# Project_Canary_V3_5.net
KiCad netlist of a schematic drawn in EAGLE
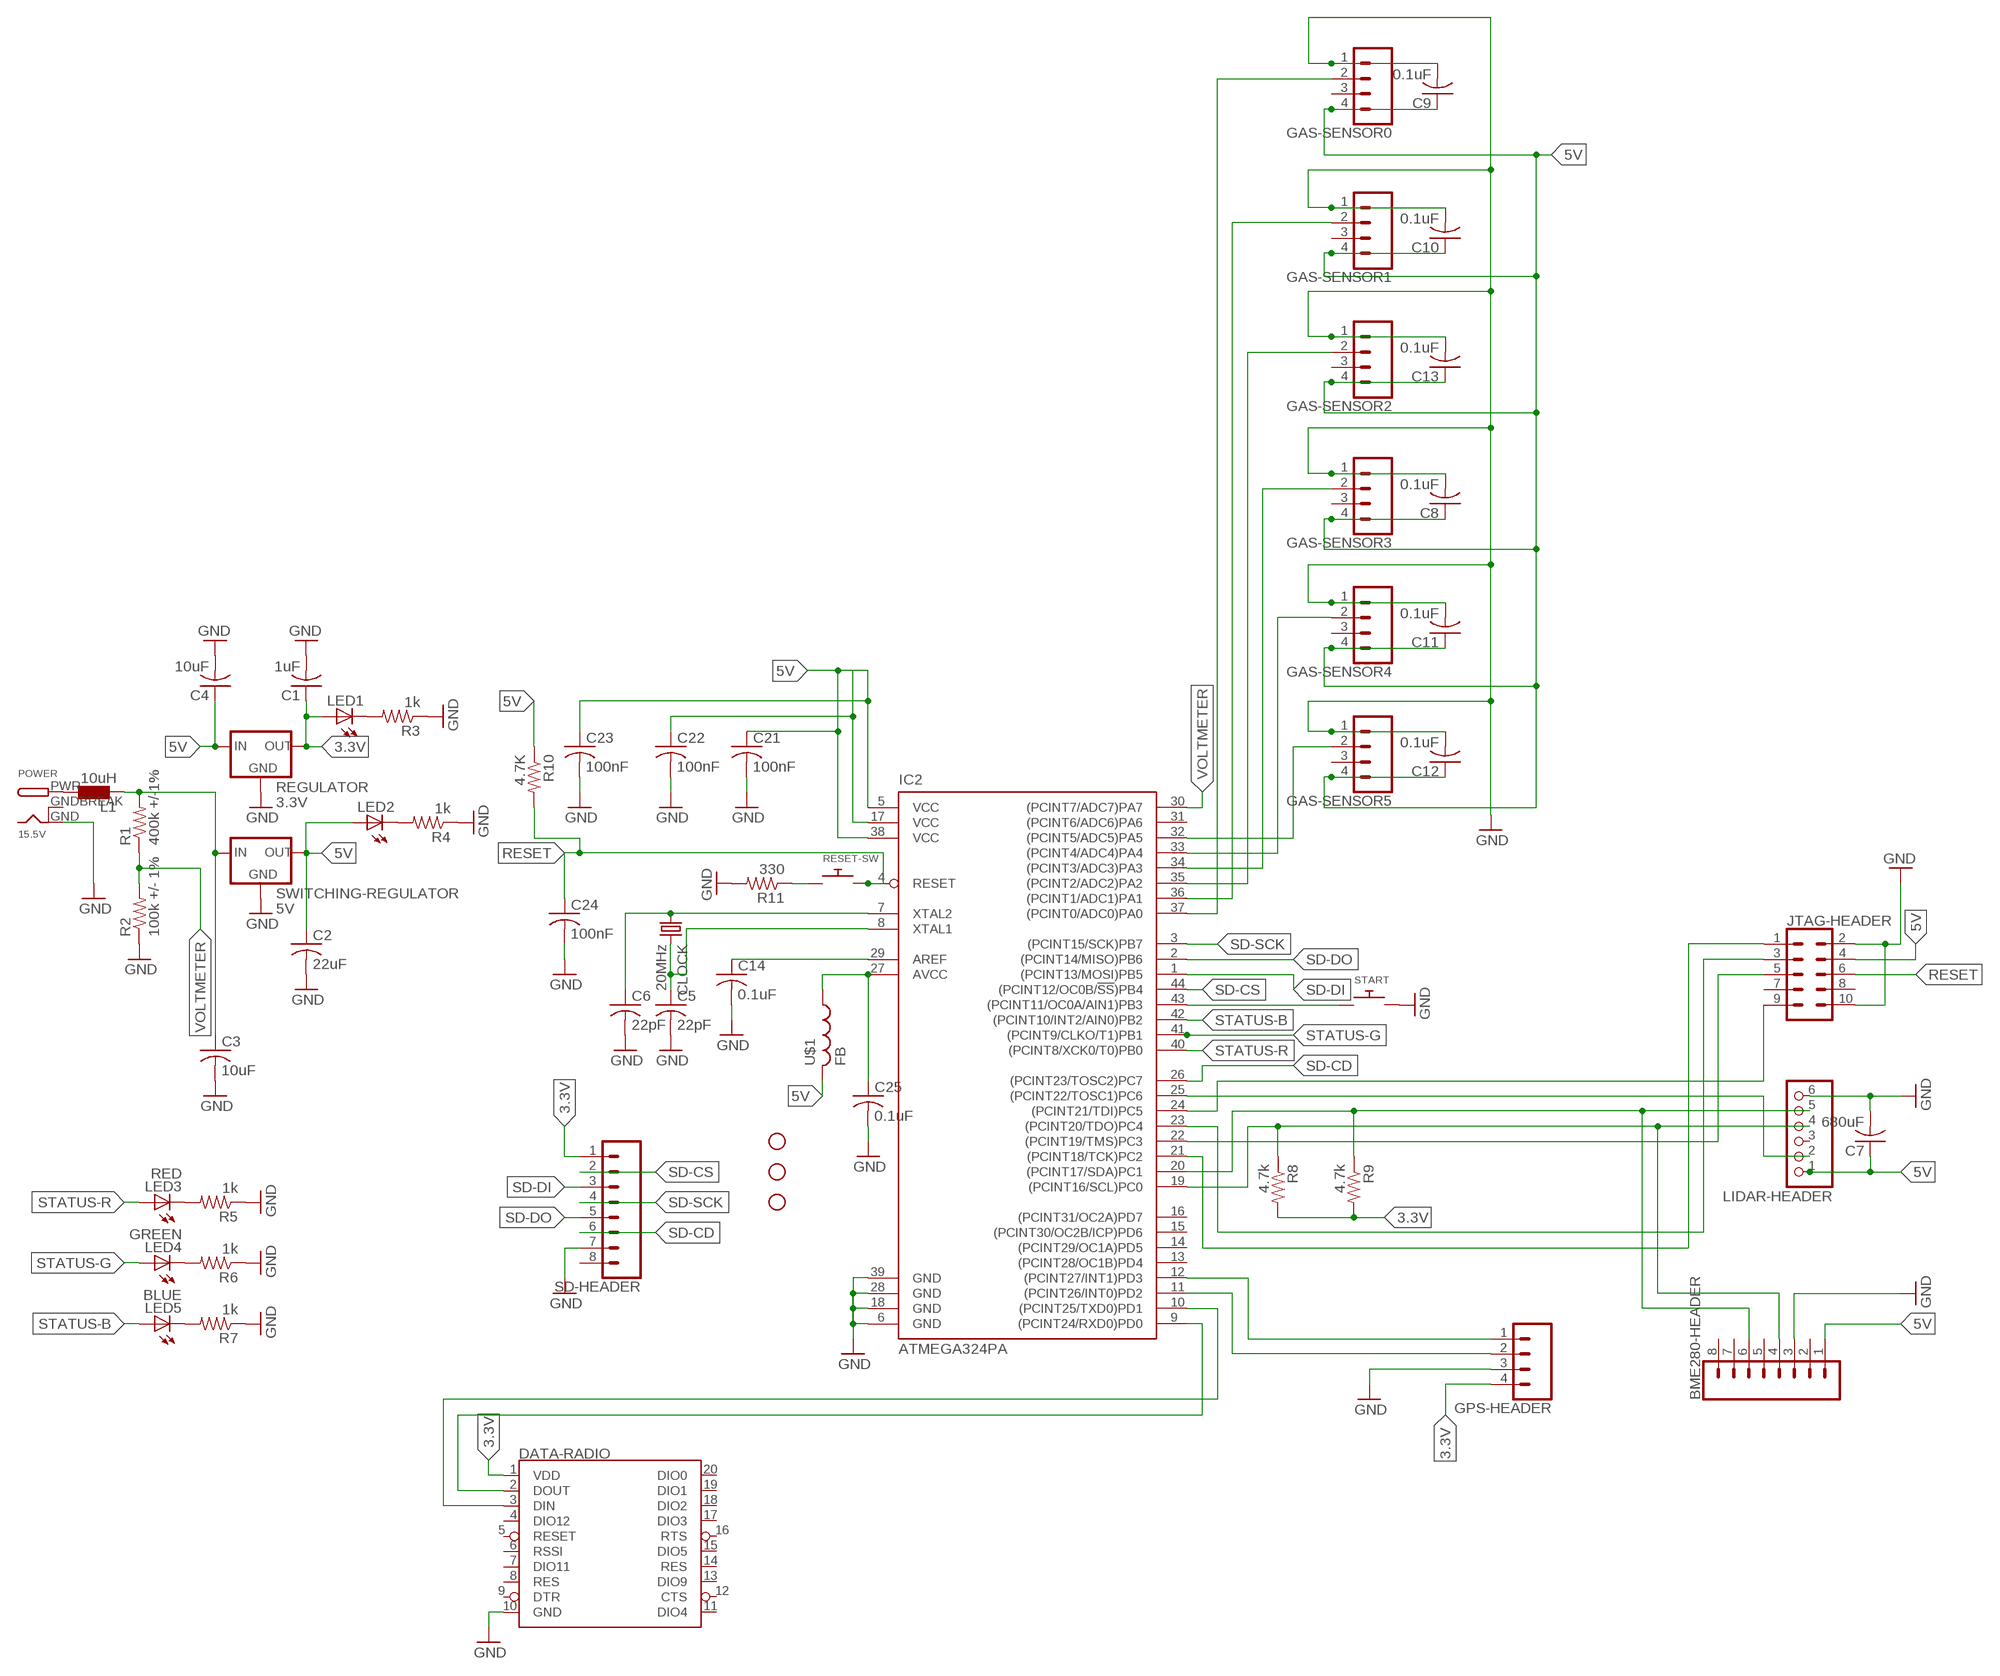
[diagram p0: schematic, sheet 1]

(export (version "E")
  (design (tool "Eeschema 10.0.6"))
  (components
    (comp (ref "BME280-HEADER")
      (value "CONN_08\"")
      (footprint "eagle-import:1X08")
      (libsource (lib "eagle-import") (part "CONN_08{dblquote}"))
    )
    (comp (ref "C1")
      (value "1uF")
      (footprint "eagle-import:C0805")
      (libsource (lib "eagle-import") (part "C-USC0805"))
    )
    (comp (ref "C2")
      (value "22uF")
      (footprint "eagle-import:C0603")
      (libsource (lib "eagle-import") (part "C-USC0603"))
    )
    (comp (ref "C3")
      (value "10uF")
      (footprint "eagle-import:C0805")
      (libsource (lib "eagle-import") (part "C-USC0805"))
    )
    (comp (ref "C4")
      (value "10uF")
      (footprint "eagle-import:C0603")
      (libsource (lib "eagle-import") (part "C-USC0603"))
    )
    (comp (ref "C5")
      (value "22pF")
      (footprint "eagle-import:C0603")
      (libsource (lib "eagle-import") (part "C-USC0603"))
    )
    (comp (ref "C6")
      (value "22pF")
      (footprint "eagle-import:C0603")
      (libsource (lib "eagle-import") (part "C-USC0603"))
    )
    (comp (ref "C7")
      (value "680uF")
      (footprint "eagle-import:C0603")
      (libsource (lib "eagle-import") (part "C-USC0603"))
    )
    (comp (ref "C8")
      (value "0.1uF")
      (footprint "eagle-import:C0603")
      (libsource (lib "eagle-import") (part "C-USC0603"))
    )
    (comp (ref "C9")
      (value "0.1uF")
      (footprint "eagle-import:C0603")
      (libsource (lib "eagle-import") (part "C-USC0603"))
    )
    (comp (ref "C10")
      (value "0.1uF")
      (footprint "eagle-import:C0603")
      (libsource (lib "eagle-import") (part "C-USC0603"))
    )
    (comp (ref "C11")
      (value "0.1uF")
      (footprint "eagle-import:C0603")
      (libsource (lib "eagle-import") (part "C-USC0603"))
    )
    (comp (ref "C12")
      (value "0.1uF")
      (footprint "eagle-import:C0603")
      (libsource (lib "eagle-import") (part "C-USC0603"))
    )
    (comp (ref "C13")
      (value "0.1uF")
      (footprint "eagle-import:C0603")
      (libsource (lib "eagle-import") (part "C-USC0603"))
    )
    (comp (ref "C14")
      (value "0.1uF")
      (footprint "eagle-import:C0603")
      (libsource (lib "eagle-import") (part "C-USC0603"))
    )
    (comp (ref "C21")
      (value "100nF")
      (footprint "eagle-import:C0603")
      (libsource (lib "eagle-import") (part "C-USC0603"))
    )
    (comp (ref "C22")
      (value "100nF")
      (footprint "eagle-import:C0603")
      (libsource (lib "eagle-import") (part "C-USC0603"))
    )
    (comp (ref "C23")
      (value "100nF")
      (footprint "eagle-import:C0603")
      (libsource (lib "eagle-import") (part "C-USC0603"))
    )
    (comp (ref "C24")
      (value "100nF")
      (footprint "eagle-import:C0805")
      (libsource (lib "eagle-import") (part "C-USC0805"))
    )
    (comp (ref "C25")
      (value "0.1uF")
      (footprint "eagle-import:C0603")
      (libsource (lib "eagle-import") (part "C-USC0603"))
    )
    (comp (ref "CLOCK")
      (value "20MHz")
      (footprint "eagle-import:86SMX")
      (libsource (lib "eagle-import") (part "CRYSTAL68SMX"))
    )
    (comp (ref "DATA-RADIO")
      (value "XBEE")
      (footprint "eagle-import:XBEE")
      (libsource (lib "eagle-import") (part "XBEE"))
    )
    (comp (ref "GAS-SENSOR0")
      (value "CONN_04")
      (footprint "eagle-import:1X04")
      (libsource (lib "eagle-import") (part "CONN_04"))
    )
    (comp (ref "GAS-SENSOR1")
      (value "CONN_04")
      (footprint "eagle-import:1X04")
      (libsource (lib "eagle-import") (part "CONN_04"))
    )
    (comp (ref "GAS-SENSOR2")
      (value "CONN_04")
      (footprint "eagle-import:1X04")
      (libsource (lib "eagle-import") (part "CONN_04"))
    )
    (comp (ref "GAS-SENSOR3")
      (value "CONN_04")
      (footprint "eagle-import:1X04")
      (libsource (lib "eagle-import") (part "CONN_04"))
    )
    (comp (ref "GAS-SENSOR4")
      (value "CONN_04")
      (footprint "eagle-import:1X04")
      (libsource (lib "eagle-import") (part "CONN_04"))
    )
    (comp (ref "GAS-SENSOR5")
      (value "CONN_04")
      (footprint "eagle-import:1X04")
      (libsource (lib "eagle-import") (part "CONN_04"))
    )
    (comp (ref "GPS-HEADER")
      (value "CONN_04")
      (footprint "eagle-import:1X04")
      (libsource (lib "eagle-import") (part "CONN_04"))
    )
    (comp (ref "IC2")
      (value "ATMEGA324PA")
      (footprint "eagle-import:TQFP44")
      (fields (field (name "MPN") "ATMEGA644PV-10AU"))
      (libsource (lib "eagle-import") (part "ATMEGA644A"))
    )
    (comp (ref "JTAG-HEADER")
      (value "CONN_05X2PTH")
      (footprint "eagle-import:2X5")
      (libsource (lib "eagle-import") (part "CONN_05X2PTH"))
    )
    (comp (ref "L1")
      (value "10uH")
      (footprint "eagle-import:L1812")
      (libsource (lib "eagle-import") (part "L"))
    )
    (comp (ref "LED1")
      (value "LEDCHIP-LED0805")
      (footprint "eagle-import:CHIP-LED0805")
      (libsource (lib "eagle-import") (part "LEDCHIP-LED0805"))
    )
    (comp (ref "LED2")
      (value "LEDCHIP-LED0805")
      (footprint "eagle-import:CHIP-LED0805")
      (libsource (lib "eagle-import") (part "LEDCHIP-LED0805"))
    )
    (comp (ref "LED3")
      (value "RED")
      (footprint "eagle-import:CHIP-LED0805")
      (libsource (lib "eagle-import") (part "LEDCHIP-LED0805"))
    )
    (comp (ref "LED4")
      (value "GREEN")
      (footprint "eagle-import:CHIP-LED0805")
      (libsource (lib "eagle-import") (part "LEDCHIP-LED0805"))
    )
    (comp (ref "LED5")
      (value "BLUE")
      (footprint "eagle-import:CHIP-LED0805")
      (libsource (lib "eagle-import") (part "LEDCHIP-LED0805"))
    )
    (comp (ref "LIDAR-HEADER")
      (value "PINHD-1X6")
      (footprint "eagle-import:1X06")
      (libsource (lib "eagle-import") (part "PINHD-1X6"))
    )
    (comp (ref "MOUNT-HOLE1")
      (value "STAND-OFF")
      (footprint "eagle-import:STAND-OFF")
      (libsource (lib "eagle-import") (part "STAND-OFF"))
    )
    (comp (ref "MOUNT-HOLE2")
      (value "STAND-OFF")
      (footprint "eagle-import:STAND-OFF")
      (libsource (lib "eagle-import") (part "STAND-OFF"))
    )
    (comp (ref "MOUNT-HOLE3")
      (value "STAND-OFF")
      (footprint "eagle-import:STAND-OFF")
      (libsource (lib "eagle-import") (part "STAND-OFF"))
    )
    (comp (ref "POWER")
      (value "15.5V")
      (footprint "eagle-import:DCJACK_2MM_PTH")
      (libsource (lib "eagle-import") (part "DCBARRELPTH"))
    )
    (comp (ref "R1")
      (value "400k +/-1%")
      (footprint "eagle-import:M0805")
      (libsource (lib "eagle-import") (part "R-US_M0805"))
    )
    (comp (ref "R2")
      (value "100k +/- 1%")
      (footprint "eagle-import:M0805")
      (libsource (lib "eagle-import") (part "R-US_M0805"))
    )
    (comp (ref "R3")
      (value "1k")
      (footprint "eagle-import:M0805")
      (libsource (lib "eagle-import") (part "R-US_M0805"))
    )
    (comp (ref "R4")
      (value "1k")
      (footprint "eagle-import:M0805")
      (libsource (lib "eagle-import") (part "R-US_M0805"))
    )
    (comp (ref "R5")
      (value "1k")
      (footprint "eagle-import:M0805")
      (libsource (lib "eagle-import") (part "R-US_M0805"))
    )
    (comp (ref "R6")
      (value "1k")
      (footprint "eagle-import:M0805")
      (libsource (lib "eagle-import") (part "R-US_M0805"))
    )
    (comp (ref "R7")
      (value "1k")
      (footprint "eagle-import:M0805")
      (libsource (lib "eagle-import") (part "R-US_M0805"))
    )
    (comp (ref "R8")
      (value "4.7k")
      (footprint "eagle-import:M0805")
      (libsource (lib "eagle-import") (part "R-US_M0805"))
    )
    (comp (ref "R9")
      (value "4.7k")
      (footprint "eagle-import:M0805")
      (libsource (lib "eagle-import") (part "R-US_M0805"))
    )
    (comp (ref "R10")
      (value "4.7K")
      (footprint "eagle-import:M0805")
      (libsource (lib "eagle-import") (part "R-US_M0805"))
    )
    (comp (ref "R11")
      (value "330")
      (footprint "eagle-import:M0805")
      (libsource (lib "eagle-import") (part "R-US_M0805"))
    )
    (comp (ref "REGULATOR")
      (value "3.3V")
      (footprint "eagle-import:TO220-IGO")
      (libsource (lib "eagle-import") (part "V_REG_78XXSINK"))
    )
    (comp (ref "RESET-SW")
      (value "SWITCH_PUSHBUTTONSOFTTOUCHSMD_SJ")
      (footprint "eagle-import:PUSHBUTTON_SMD_SJ")
      (libsource (lib "eagle-import") (part "SWITCH_PUSHBUTTONSOFTTOUCHSMD_SJ"))
    )
    (comp (ref "SD-HEADER")
      (value "CONN_08\"")
      (footprint "eagle-import:1X08")
      (libsource (lib "eagle-import") (part "CONN_08{dblquote}"))
    )
    (comp (ref "START")
      (value "SWITCH_PUSHBUTTONSOFTTOUCHSMD_SJ")
      (footprint "eagle-import:PUSHBUTTON_SMD_SJ")
      (libsource (lib "eagle-import") (part "SWITCH_PUSHBUTTONSOFTTOUCHSMD_SJ"))
    )
    (comp (ref "SWITCHING-REGULATOR")
      (value "5V")
      (footprint "eagle-import:TO220-IGO")
      (libsource (lib "eagle-import") (part "V_REG_78XXSINK"))
    )
    (comp (ref "U$1") (value "FB") (footprint "eagle-import:FB") (libsource (lib "eagle-import") (part "FB")))
  )
  (nets
    (net (code "1") (name "/GNDBREAK") (class "Default")
      (node (ref "POWER") (pin "GNDBREAK") (pinfunction "GNDBREAK_GNDBREAK") (pintype "power_in"))
    )
    (net (code "2") (name "3.3V") (class "Default")
      (node (ref "C1") (pin "1") (pinfunction "1_1") (pintype "passive"))
      (node (ref "DATA-RADIO") (pin "1") (pinfunction "VDD_1") (pintype "power_in"))
      (node (ref "GPS-HEADER") (pin "4") (pinfunction "4_4") (pintype "passive"))
      (node (ref "LED1") (pin "A") (pinfunction "A_A") (pintype "passive"))
      (node (ref "R8") (pin "2") (pinfunction "2_2") (pintype "passive"))
      (node (ref "R9") (pin "2") (pinfunction "2_2") (pintype "passive"))
      (node (ref "REGULATOR") (pin "OUT") (pinfunction "OUT_OUT") (pintype "passive"))
      (node (ref "SD-HEADER") (pin "1") (pinfunction "1_1") (pintype "passive"))
    )
    (net (code "3") (name "5V") (class "Default")
      (node (ref "BME280-HEADER") (pin "1") (pinfunction "1_1") (pintype "passive"))
      (node (ref "C10") (pin "1") (pinfunction "1_1") (pintype "passive"))
      (node (ref "C11") (pin "1") (pinfunction "1_1") (pintype "passive"))
      (node (ref "C12") (pin "1") (pinfunction "1_1") (pintype "passive"))
      (node (ref "C13") (pin "1") (pinfunction "1_1") (pintype "passive"))
      (node (ref "C2") (pin "1") (pinfunction "1_1") (pintype "passive"))
      (node (ref "C21") (pin "1") (pinfunction "1_1") (pintype "passive"))
      (node (ref "C22") (pin "1") (pinfunction "1_1") (pintype "passive"))
      (node (ref "C23") (pin "1") (pinfunction "1_1") (pintype "passive"))
      (node (ref "C25") (pin "1") (pinfunction "1_1") (pintype "passive"))
      (node (ref "C4") (pin "1") (pinfunction "1_1") (pintype "passive"))
      (node (ref "C7") (pin "1") (pinfunction "1_1") (pintype "passive"))
      (node (ref "C8") (pin "1") (pinfunction "1_1") (pintype "passive"))
      (node (ref "C9") (pin "1") (pinfunction "1_1") (pintype "passive"))
      (node (ref "GAS-SENSOR0") (pin "4") (pinfunction "4_4") (pintype "passive"))
      (node (ref "GAS-SENSOR1") (pin "4") (pinfunction "4_4") (pintype "passive"))
      (node (ref "GAS-SENSOR2") (pin "4") (pinfunction "4_4") (pintype "passive"))
      (node (ref "GAS-SENSOR3") (pin "4") (pinfunction "4_4") (pintype "passive"))
      (node (ref "GAS-SENSOR4") (pin "4") (pinfunction "4_4") (pintype "passive"))
      (node (ref "GAS-SENSOR5") (pin "4") (pinfunction "4_4") (pintype "passive"))
      (node (ref "IC2") (pin "17") (pinfunction "VCC_17") (pintype "power_in"))
      (node (ref "IC2") (pin "27") (pinfunction "AVCC_27") (pintype "power_in"))
      (node (ref "IC2") (pin "38") (pinfunction "VCC_38") (pintype "power_in"))
      (node (ref "IC2") (pin "5") (pinfunction "VCC_5") (pintype "power_in"))
      (node (ref "JTAG-HEADER") (pin "4") (pinfunction "4_4") (pintype "passive"))
      (node (ref "LED2") (pin "A") (pinfunction "A_A") (pintype "passive"))
      (node (ref "LIDAR-HEADER") (pin "1") (pinfunction "1_1") (pintype "passive"))
      (node (ref "REGULATOR") (pin "IN") (pinfunction "IN_IN") (pintype "input"))
      (node (ref "SWITCHING-REGULATOR") (pin "OUT") (pinfunction "OUT_OUT") (pintype "passive"))
      (node (ref "U$1") (pin "P$1") (pinfunction "1_P$1") (pintype "passive"))
    )
    (net (code "4") (name "GND") (class "Default")
      (node (ref "BME280-HEADER") (pin "3") (pinfunction "3_3") (pintype "passive"))
      (node (ref "C1") (pin "2") (pinfunction "2_2") (pintype "passive"))
      (node (ref "C10") (pin "2") (pinfunction "2_2") (pintype "passive"))
      (node (ref "C11") (pin "2") (pinfunction "2_2") (pintype "passive"))
      (node (ref "C12") (pin "2") (pinfunction "2_2") (pintype "passive"))
      (node (ref "C13") (pin "2") (pinfunction "2_2") (pintype "passive"))
      (node (ref "C14") (pin "2") (pinfunction "2_2") (pintype "passive"))
      (node (ref "C2") (pin "2") (pinfunction "2_2") (pintype "passive"))
      (node (ref "C21") (pin "2") (pinfunction "2_2") (pintype "passive"))
      (node (ref "C22") (pin "2") (pinfunction "2_2") (pintype "passive"))
      (node (ref "C23") (pin "2") (pinfunction "2_2") (pintype "passive"))
      (node (ref "C24") (pin "2") (pinfunction "2_2") (pintype "passive"))
      (node (ref "C25") (pin "2") (pinfunction "2_2") (pintype "passive"))
      (node (ref "C3") (pin "2") (pinfunction "2_2") (pintype "passive"))
      (node (ref "C4") (pin "2") (pinfunction "2_2") (pintype "passive"))
      (node (ref "C5") (pin "2") (pinfunction "2_2") (pintype "passive"))
      (node (ref "C6") (pin "2") (pinfunction "2_2") (pintype "passive"))
      (node (ref "C7") (pin "2") (pinfunction "2_2") (pintype "passive"))
      (node (ref "C8") (pin "2") (pinfunction "2_2") (pintype "passive"))
      (node (ref "C9") (pin "2") (pinfunction "2_2") (pintype "passive"))
      (node (ref "DATA-RADIO") (pin "10") (pinfunction "GND_10") (pintype "power_in"))
      (node (ref "GAS-SENSOR0") (pin "1") (pinfunction "1_1") (pintype "passive"))
      (node (ref "GAS-SENSOR1") (pin "1") (pinfunction "1_1") (pintype "passive"))
      (node (ref "GAS-SENSOR2") (pin "1") (pinfunction "1_1") (pintype "passive"))
      (node (ref "GAS-SENSOR3") (pin "1") (pinfunction "1_1") (pintype "passive"))
      (node (ref "GAS-SENSOR4") (pin "1") (pinfunction "1_1") (pintype "passive"))
      (node (ref "GAS-SENSOR5") (pin "1") (pinfunction "1_1") (pintype "passive"))
      (node (ref "GPS-HEADER") (pin "3") (pinfunction "3_3") (pintype "passive"))
      (node (ref "IC2") (pin "18") (pinfunction "GND_18") (pintype "power_in"))
      (node (ref "IC2") (pin "28") (pinfunction "GND_28") (pintype "power_in"))
      (node (ref "IC2") (pin "39") (pinfunction "GND_39") (pintype "power_in"))
      (node (ref "IC2") (pin "6") (pinfunction "GND_6") (pintype "power_in"))
      (node (ref "JTAG-HEADER") (pin "10") (pinfunction "10_10") (pintype "passive"))
      (node (ref "JTAG-HEADER") (pin "2") (pinfunction "2_2") (pintype "passive"))
      (node (ref "LIDAR-HEADER") (pin "6") (pinfunction "6_6") (pintype "passive"))
      (node (ref "POWER") (pin "GND") (pinfunction "GND_GND") (pintype "power_in"))
      (node (ref "R11") (pin "2") (pinfunction "2_2") (pintype "passive"))
      (node (ref "R2") (pin "1") (pinfunction "1_1") (pintype "passive"))
      (node (ref "R3") (pin "1") (pinfunction "1_1") (pintype "passive"))
      (node (ref "R4") (pin "1") (pinfunction "1_1") (pintype "passive"))
      (node (ref "R5") (pin "1") (pinfunction "1_1") (pintype "passive"))
      (node (ref "R6") (pin "1") (pinfunction "1_1") (pintype "passive"))
      (node (ref "R7") (pin "1") (pinfunction "1_1") (pintype "passive"))
      (node (ref "REGULATOR") (pin "GND") (pinfunction "GND_GND") (pintype "input"))
      (node (ref "SD-HEADER") (pin "7") (pinfunction "7_7") (pintype "passive"))
      (node (ref "START") (pin "P$2") (pinfunction "P$2_P$2") (pintype "passive"))
      (node (ref "SWITCHING-REGULATOR") (pin "GND") (pinfunction "GND_GND") (pintype "input"))
    )
    (net (code "5") (name "Net-(C3-Pad1)") (class "Default")
      (node (ref "C3") (pin "1") (pinfunction "1_1") (pintype "passive"))
      (node (ref "L1") (pin "2") (pinfunction "2_2") (pintype "passive"))
      (node (ref "R1") (pin "2") (pinfunction "2_2") (pintype "passive"))
      (node (ref "SWITCHING-REGULATOR") (pin "IN") (pinfunction "IN_IN") (pintype "input"))
    )
    (net (code "6") (name "Net-(CLOCK-2)") (class "Default")
      (node (ref "C5") (pin "1") (pinfunction "1_1") (pintype "passive"))
      (node (ref "CLOCK") (pin "4") (pinfunction "2_4") (pintype "passive"))
      (node (ref "IC2") (pin "8") (pinfunction "XTAL1_8") (pintype "bidirectional"))
    )
    (net (code "7") (name "Net-(DATA-RADIO-DIN)") (class "Default")
      (node (ref "DATA-RADIO") (pin "3") (pinfunction "DIN_3") (pintype "input"))
      (node (ref "IC2") (pin "10") (pinfunction "(PCINT25/TXD0)PD1_10") (pintype "bidirectional"))
    )
    (net (code "8") (name "Net-(DATA-RADIO-DOUT)") (class "Default")
      (node (ref "DATA-RADIO") (pin "2") (pinfunction "DOUT_2") (pintype "output"))
      (node (ref "IC2") (pin "9") (pinfunction "(PCINT24/RXD0)PD0_9") (pintype "bidirectional"))
    )
    (net (code "9") (name "Net-(IC2-(PCINT0{slash}ADC0)PA0)") (class "Default")
      (node (ref "GAS-SENSOR0") (pin "2") (pinfunction "2_2") (pintype "passive"))
      (node (ref "IC2") (pin "37") (pinfunction "(PCINT0/ADC0)PA0_37") (pintype "bidirectional"))
    )
    (net (code "10") (name "Net-(IC2-(PCINT1{slash}ADC1)PA1)") (class "Default")
      (node (ref "GAS-SENSOR1") (pin "2") (pinfunction "2_2") (pintype "passive"))
      (node (ref "IC2") (pin "36") (pinfunction "(PCINT1/ADC1)PA1_36") (pintype "bidirectional"))
    )
    (net (code "11") (name "Net-(IC2-(PCINT2{slash}ADC2)PA2)") (class "Default")
      (node (ref "GAS-SENSOR2") (pin "2") (pinfunction "2_2") (pintype "passive"))
      (node (ref "IC2") (pin "35") (pinfunction "(PCINT2/ADC2)PA2_35") (pintype "bidirectional"))
    )
    (net (code "12") (name "Net-(IC2-(PCINT3{slash}ADC3)PA3)") (class "Default")
      (node (ref "GAS-SENSOR3") (pin "2") (pinfunction "2_2") (pintype "passive"))
      (node (ref "IC2") (pin "34") (pinfunction "(PCINT3/ADC3)PA3_34") (pintype "bidirectional"))
    )
    (net (code "13") (name "Net-(IC2-(PCINT4{slash}ADC4)PA4)") (class "Default")
      (node (ref "GAS-SENSOR4") (pin "2") (pinfunction "2_2") (pintype "passive"))
      (node (ref "IC2") (pin "33") (pinfunction "(PCINT4/ADC4)PA4_33") (pintype "bidirectional"))
    )
    (net (code "14") (name "Net-(IC2-(PCINT5{slash}ADC5)PA5)") (class "Default")
      (node (ref "GAS-SENSOR5") (pin "2") (pinfunction "2_2") (pintype "passive"))
      (node (ref "IC2") (pin "32") (pinfunction "(PCINT5/ADC5)PA5_32") (pintype "bidirectional"))
    )
    (net (code "15") (name "Net-(IC2-(PCINT11{slash}OC0A{slash}AIN1)PB3)") (class "Default")
      (node (ref "IC2") (pin "43") (pinfunction "(PCINT11/OC0A/AIN1)PB3_43") (pintype "bidirectional"))
      (node (ref "START") (pin "P$1") (pinfunction "P$1_P$1") (pintype "passive"))
    )
    (net (code "16") (name "Net-(IC2-(PCINT16{slash}SCL)PC0)") (class "Default")
      (node (ref "BME280-HEADER") (pin "4") (pinfunction "4_4") (pintype "passive"))
      (node (ref "IC2") (pin "19") (pinfunction "(PCINT16/SCL)PC0_19") (pintype "output"))
      (node (ref "LIDAR-HEADER") (pin "4") (pinfunction "4_4") (pintype "passive"))
      (node (ref "R8") (pin "1") (pinfunction "1_1") (pintype "passive"))
    )
    (net (code "17") (name "Net-(IC2-(PCINT17{slash}SDA)PC1)") (class "Default")
      (node (ref "BME280-HEADER") (pin "6") (pinfunction "6_6") (pintype "passive"))
      (node (ref "IC2") (pin "20") (pinfunction "(PCINT17/SDA)PC1_20") (pintype "output"))
      (node (ref "LIDAR-HEADER") (pin "5") (pinfunction "5_5") (pintype "passive"))
      (node (ref "R9") (pin "1") (pinfunction "1_1") (pintype "passive"))
    )
    (net (code "18") (name "Net-(IC2-(PCINT18{slash}TCK)PC2)") (class "Default")
      (node (ref "IC2") (pin "21") (pinfunction "(PCINT18/TCK)PC2_21") (pintype "output"))
      (node (ref "JTAG-HEADER") (pin "1") (pinfunction "1_1") (pintype "passive"))
    )
    (net (code "19") (name "Net-(IC2-(PCINT19{slash}TMS)PC3)") (class "Default")
      (node (ref "IC2") (pin "22") (pinfunction "(PCINT19/TMS)PC3_22") (pintype "output"))
      (node (ref "JTAG-HEADER") (pin "5") (pinfunction "5_5") (pintype "passive"))
    )
    (net (code "20") (name "Net-(IC2-(PCINT20{slash}TDO)PC4)") (class "Default")
      (node (ref "IC2") (pin "23") (pinfunction "(PCINT20/TDO)PC4_23") (pintype "output"))
      (node (ref "JTAG-HEADER") (pin "3") (pinfunction "3_3") (pintype "passive"))
    )
    (net (code "21") (name "Net-(IC2-(PCINT21{slash}TDI)PC5)") (class "Default")
      (node (ref "IC2") (pin "24") (pinfunction "(PCINT21/TDI)PC5_24") (pintype "output"))
      (node (ref "JTAG-HEADER") (pin "9") (pinfunction "9_9") (pintype "passive"))
    )
    (net (code "22") (name "Net-(IC2-(PCINT22{slash}TOSC1)PC6)") (class "Default")
      (node (ref "IC2") (pin "25") (pinfunction "(PCINT22/TOSC1)PC6_25") (pintype "output"))
      (node (ref "LIDAR-HEADER") (pin "2") (pinfunction "2_2") (pintype "passive"))
    )
    (net (code "23") (name "Net-(IC2-(PCINT26{slash}INT0)PD2)") (class "Default")
      (node (ref "GPS-HEADER") (pin "2") (pinfunction "2_2") (pintype "passive"))
      (node (ref "IC2") (pin "11") (pinfunction "(PCINT26/INT0)PD2_11") (pintype "bidirectional"))
    )
    (net (code "24") (name "Net-(IC2-(PCINT27{slash}INT1)PD3)") (class "Default")
      (node (ref "GPS-HEADER") (pin "1") (pinfunction "1_1") (pintype "passive"))
      (node (ref "IC2") (pin "12") (pinfunction "(PCINT27/INT1)PD3_12") (pintype "bidirectional"))
    )
    (net (code "25") (name "Net-(IC2-AREF)") (class "Default")
      (node (ref "C14") (pin "1") (pinfunction "1_1") (pintype "passive"))
      (node (ref "IC2") (pin "29") (pinfunction "AREF_29") (pintype "passive"))
    )
    (net (code "26") (name "Net-(IC2-XTAL2)") (class "Default")
      (node (ref "C6") (pin "1") (pinfunction "1_1") (pintype "passive"))
      (node (ref "CLOCK") (pin "1") (pinfunction "1_1") (pintype "passive"))
      (node (ref "IC2") (pin "7") (pinfunction "XTAL2_7") (pintype "bidirectional"))
    )
    (net (code "27") (name "Net-(L1-Pad1)") (class "Default")
      (node (ref "L1") (pin "1") (pinfunction "1_1") (pintype "passive"))
      (node (ref "POWER") (pin "PWR") (pinfunction "PWR_PWR") (pintype "power_in"))
    )
    (net (code "28") (name "Net-(LED1-PadC)") (class "Default")
      (node (ref "LED1") (pin "C") (pinfunction "C_C") (pintype "passive"))
      (node (ref "R3") (pin "2") (pinfunction "2_2") (pintype "passive"))
    )
    (net (code "29") (name "Net-(LED2-PadC)") (class "Default")
      (node (ref "LED2") (pin "C") (pinfunction "C_C") (pintype "passive"))
      (node (ref "R4") (pin "2") (pinfunction "2_2") (pintype "passive"))
    )
    (net (code "30") (name "Net-(LED3-PadC)") (class "Default")
      (node (ref "LED3") (pin "C") (pinfunction "C_C") (pintype "passive"))
      (node (ref "R5") (pin "2") (pinfunction "2_2") (pintype "passive"))
    )
    (net (code "31") (name "Net-(LED4-PadC)") (class "Default")
      (node (ref "LED4") (pin "C") (pinfunction "C_C") (pintype "passive"))
      (node (ref "R6") (pin "2") (pinfunction "2_2") (pintype "passive"))
    )
    (net (code "32") (name "Net-(LED5-PadC)") (class "Default")
      (node (ref "LED5") (pin "C") (pinfunction "C_C") (pintype "passive"))
      (node (ref "R7") (pin "2") (pinfunction "2_2") (pintype "passive"))
    )
    (net (code "33") (name "Net-(R11-Pad1)") (class "Default")
      (node (ref "R11") (pin "1") (pinfunction "1_1") (pintype "passive"))
      (node (ref "RESET-SW") (pin "P$1") (pinfunction "P$1_P$1") (pintype "passive"))
    )
    (net (code "34") (name "RESET") (class "Default")
      (node (ref "C24") (pin "1") (pinfunction "1_1") (pintype "passive"))
      (node (ref "IC2") (pin "4") (pinfunction "RESET_4") (pintype "input"))
      (node (ref "JTAG-HEADER") (pin "6") (pinfunction "6_6") (pintype "passive"))
      (node (ref "R10") (pin "2") (pinfunction "2_2") (pintype "passive"))
      (node (ref "RESET-SW") (pin "P$2") (pinfunction "P$2_P$2") (pintype "passive"))
    )
    (net (code "35") (name "SD-CD") (class "Default")
      (node (ref "IC2") (pin "26") (pinfunction "(PCINT23/TOSC2)PC7_26") (pintype "output"))
      (node (ref "SD-HEADER") (pin "6") (pinfunction "6_6") (pintype "passive"))
    )
    (net (code "36") (name "SD-CS") (class "Default")
      (node (ref "IC2") (pin "44") (pinfunction "(PCINT12/OC0B/~{SS})PB4_44") (pintype "bidirectional"))
      (node (ref "SD-HEADER") (pin "2") (pinfunction "2_2") (pintype "passive"))
    )
    (net (code "37") (name "SD-DI") (class "Default")
      (node (ref "IC2") (pin "1") (pinfunction "(PCINT13/MOSI)PB5_1") (pintype "bidirectional"))
      (node (ref "SD-HEADER") (pin "3") (pinfunction "3_3") (pintype "passive"))
    )
    (net (code "38") (name "SD-DO") (class "Default")
      (node (ref "IC2") (pin "2") (pinfunction "(PCINT14/MISO)PB6_2") (pintype "bidirectional"))
      (node (ref "SD-HEADER") (pin "5") (pinfunction "5_5") (pintype "passive"))
    )
    (net (code "39") (name "SD-SCK") (class "Default")
      (node (ref "IC2") (pin "3") (pinfunction "(PCINT15/SCK)PB7_3") (pintype "bidirectional"))
      (node (ref "SD-HEADER") (pin "4") (pinfunction "4_4") (pintype "passive"))
    )
    (net (code "40") (name "STATUS-B") (class "Default")
      (node (ref "IC2") (pin "42") (pinfunction "(PCINT10/INT2/AIN0)PB2_42") (pintype "bidirectional"))
      (node (ref "LED5") (pin "A") (pinfunction "A_A") (pintype "passive"))
    )
    (net (code "41") (name "STATUS-G") (class "Default")
      (node (ref "IC2") (pin "41") (pinfunction "(PCINT9/CLKO/T1)PB1_41") (pintype "bidirectional"))
      (node (ref "LED4") (pin "A") (pinfunction "A_A") (pintype "passive"))
    )
    (net (code "42") (name "STATUS-R") (class "Default")
      (node (ref "IC2") (pin "40") (pinfunction "(PCINT8/XCK0/T0)PB0_40") (pintype "bidirectional"))
      (node (ref "LED3") (pin "A") (pinfunction "A_A") (pintype "passive"))
    )
    (net (code "43") (name "VOLTMETER") (class "Default")
      (node (ref "IC2") (pin "30") (pinfunction "(PCINT7/ADC7)PA7_30") (pintype "bidirectional"))
      (node (ref "R1") (pin "1") (pinfunction "1_1") (pintype "passive"))
      (node (ref "R2") (pin "2") (pinfunction "2_2") (pintype "passive"))
    )
    (net (code "44") (name "unconnected-(BME280-HEADER-Pad2)") (class "Default")
      (node (ref "BME280-HEADER") (pin "2") (pinfunction "2_2") (pintype "passive"))
    )
    (net (code "45") (name "unconnected-(BME280-HEADER-Pad5)") (class "Default")
      (node (ref "BME280-HEADER") (pin "5") (pinfunction "5_5") (pintype "passive"))
    )
    (net (code "46") (name "unconnected-(BME280-HEADER-Pad7)") (class "Default")
      (node (ref "BME280-HEADER") (pin "7") (pinfunction "7_7") (pintype "passive"))
    )
    (net (code "47") (name "unconnected-(BME280-HEADER-Pad8)") (class "Default")
      (node (ref "BME280-HEADER") (pin "8") (pinfunction "8_8") (pintype "passive"))
    )
    (net (code "48") (name "unconnected-(DATA-RADIO-CTS-Pad12)") (class "Default")
      (node (ref "DATA-RADIO") (pin "12") (pinfunction "CTS_12") (pintype "output"))
    )
    (net (code "49") (name "unconnected-(DATA-RADIO-DIO0-Pad20)") (class "Default")
      (node (ref "DATA-RADIO") (pin "20") (pinfunction "DIO0_20") (pintype "bidirectional"))
    )
    (net (code "50") (name "unconnected-(DATA-RADIO-DIO1-Pad19)") (class "Default")
      (node (ref "DATA-RADIO") (pin "19") (pinfunction "DIO1_19") (pintype "bidirectional"))
    )
    (net (code "51") (name "unconnected-(DATA-RADIO-DIO2-Pad18)") (class "Default")
      (node (ref "DATA-RADIO") (pin "18") (pinfunction "DIO2_18") (pintype "bidirectional"))
    )
    (net (code "52") (name "unconnected-(DATA-RADIO-DIO3-Pad17)") (class "Default")
      (node (ref "DATA-RADIO") (pin "17") (pinfunction "DIO3_17") (pintype "bidirectional"))
    )
    (net (code "53") (name "unconnected-(DATA-RADIO-DIO4-Pad11)") (class "Default")
      (node (ref "DATA-RADIO") (pin "11") (pinfunction "DIO4_11") (pintype "bidirectional"))
    )
    (net (code "54") (name "unconnected-(DATA-RADIO-DIO5-Pad15)") (class "Default")
      (node (ref "DATA-RADIO") (pin "15") (pinfunction "DIO5_15") (pintype "bidirectional"))
    )
    (net (code "55") (name "unconnected-(DATA-RADIO-DIO9-Pad13)") (class "Default")
      (node (ref "DATA-RADIO") (pin "13") (pinfunction "DIO9_13") (pintype "bidirectional"))
    )
    (net (code "56") (name "unconnected-(DATA-RADIO-DIO11-Pad7)") (class "Default")
      (node (ref "DATA-RADIO") (pin "7") (pinfunction "DIO11_7") (pintype "bidirectional"))
    )
    (net (code "57") (name "unconnected-(DATA-RADIO-DIO12-Pad4)") (class "Default")
      (node (ref "DATA-RADIO") (pin "4") (pinfunction "DIO12_4") (pintype "bidirectional"))
    )
    (net (code "58") (name "unconnected-(DATA-RADIO-DTR-Pad9)") (class "Default")
      (node (ref "DATA-RADIO") (pin "9") (pinfunction "DTR_9") (pintype "bidirectional"))
    )
    (net (code "59") (name "unconnected-(DATA-RADIO-RES-Pad8)") (class "Default")
      (node (ref "DATA-RADIO") (pin "8") (pinfunction "RES_8") (pintype "bidirectional"))
    )
    (net (code "60") (name "unconnected-(DATA-RADIO-RES-Pad14)") (class "Default")
      (node (ref "DATA-RADIO") (pin "14") (pinfunction "RES_14") (pintype "bidirectional"))
    )
    (net (code "61") (name "unconnected-(DATA-RADIO-RESET-Pad5)") (class "Default")
      (node (ref "DATA-RADIO") (pin "5") (pinfunction "RESET_5") (pintype "input"))
    )
    (net (code "62") (name "unconnected-(DATA-RADIO-RSSI-Pad6)") (class "Default")
      (node (ref "DATA-RADIO") (pin "6") (pinfunction "RSSI_6") (pintype "bidirectional"))
    )
    (net (code "63") (name "unconnected-(DATA-RADIO-RTS-Pad16)") (class "Default")
      (node (ref "DATA-RADIO") (pin "16") (pinfunction "RTS_16") (pintype "input"))
    )
    (net (code "64") (name "unconnected-(GAS-SENSOR0-Pad3)") (class "Default")
      (node (ref "GAS-SENSOR0") (pin "3") (pinfunction "3_3") (pintype "passive"))
    )
    (net (code "65") (name "unconnected-(GAS-SENSOR1-Pad3)") (class "Default")
      (node (ref "GAS-SENSOR1") (pin "3") (pinfunction "3_3") (pintype "passive"))
    )
    (net (code "66") (name "unconnected-(GAS-SENSOR2-Pad3)") (class "Default")
      (node (ref "GAS-SENSOR2") (pin "3") (pinfunction "3_3") (pintype "passive"))
    )
    (net (code "67") (name "unconnected-(GAS-SENSOR3-Pad3)") (class "Default")
      (node (ref "GAS-SENSOR3") (pin "3") (pinfunction "3_3") (pintype "passive"))
    )
    (net (code "68") (name "unconnected-(GAS-SENSOR4-Pad3)") (class "Default")
      (node (ref "GAS-SENSOR4") (pin "3") (pinfunction "3_3") (pintype "passive"))
    )
    (net (code "69") (name "unconnected-(GAS-SENSOR5-Pad3)") (class "Default")
      (node (ref "GAS-SENSOR5") (pin "3") (pinfunction "3_3") (pintype "passive"))
    )
    (net (code "70") (name "unconnected-(IC2-(PCINT6{slash}ADC6)PA6-Pad31)") (class "Default")
      (node (ref "IC2") (pin "31") (pinfunction "(PCINT6/ADC6)PA6_31") (pintype "bidirectional"))
    )
    (net (code "71") (name "unconnected-(IC2-(PCINT28{slash}OC1B)PD4-Pad13)") (class "Default")
      (node (ref "IC2") (pin "13") (pinfunction "(PCINT28/OC1B)PD4_13") (pintype "bidirectional"))
    )
    (net (code "72") (name "unconnected-(IC2-(PCINT29{slash}OC1A)PD5-Pad14)") (class "Default")
      (node (ref "IC2") (pin "14") (pinfunction "(PCINT29/OC1A)PD5_14") (pintype "bidirectional"))
    )
    (net (code "73") (name "unconnected-(IC2-(PCINT30{slash}OC2B{slash}ICP)PD6-Pad15)") (class "Default")
      (node (ref "IC2") (pin "15") (pinfunction "(PCINT30/OC2B/ICP)PD6_15") (pintype "bidirectional"))
    )
    (net (code "74") (name "unconnected-(IC2-(PCINT31{slash}OC2A)PD7-Pad16)") (class "Default")
      (node (ref "IC2") (pin "16") (pinfunction "(PCINT31/OC2A)PD7_16") (pintype "bidirectional"))
    )
    (net (code "75") (name "unconnected-(JTAG-HEADER-Pad7)") (class "Default")
      (node (ref "JTAG-HEADER") (pin "7") (pinfunction "7_7") (pintype "passive"))
    )
    (net (code "76") (name "unconnected-(JTAG-HEADER-Pad8)") (class "Default")
      (node (ref "JTAG-HEADER") (pin "8") (pinfunction "8_8") (pintype "passive"))
    )
    (net (code "77") (name "unconnected-(LIDAR-HEADER-Pad3)") (class "Default")
      (node (ref "LIDAR-HEADER") (pin "3") (pinfunction "3_3") (pintype "passive"))
    )
    (net (code "78") (name "unconnected-(R10-Pad1)") (class "Default")
      (node (ref "R10") (pin "1") (pinfunction "1_1") (pintype "passive"))
    )
    (net (code "79") (name "unconnected-(SD-HEADER-Pad8)") (class "Default")
      (node (ref "SD-HEADER") (pin "8") (pinfunction "8_8") (pintype "passive"))
    )
    (net (code "80") (name "unconnected-(U$1-2-PadP$2)") (class "Default")
      (node (ref "U$1") (pin "P$2") (pinfunction "2_P$2") (pintype "passive"))
    )
  )
)
